# connector.net
KiCad netlist of a schematic drawn in Altium Designer
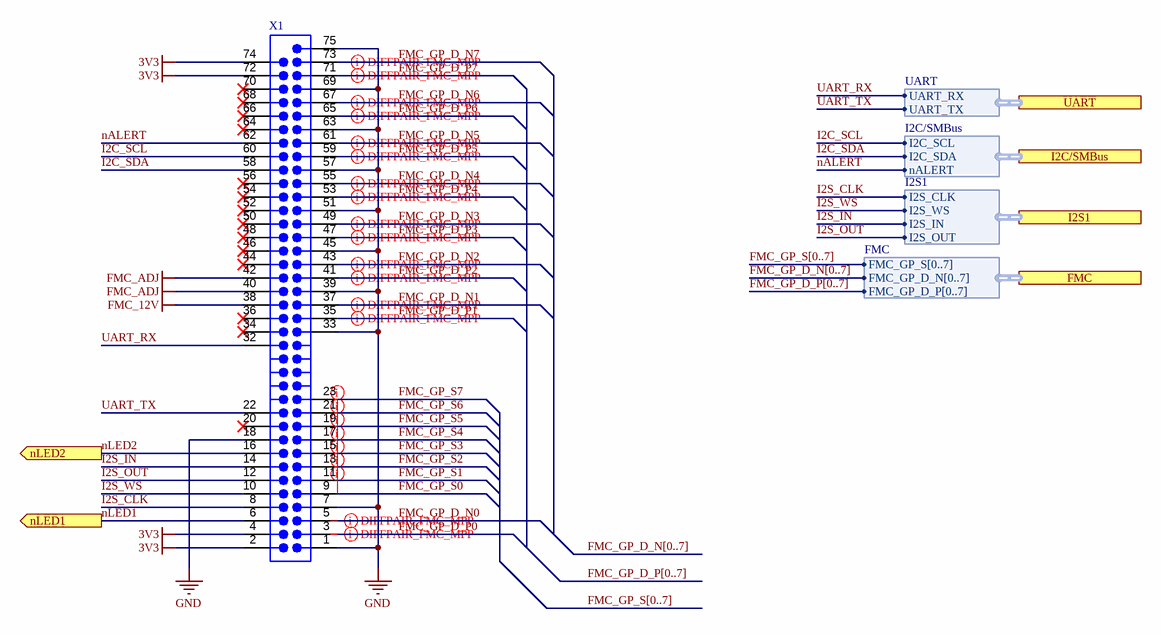
[diagram p0: connector.SchDoc]

(export (version "E")
  (design (tool "Eeschema 10.0.6"))
  (components
    (comp (ref "X1")
      (value "CONN PWR CARD EDGE PCB SLOT MALE")
      (footprint "CON-67_0.5MM_PCB_SLOT")
      (description "Mates with 2199119-4 - No BOM")
      (libsource (lib "ETHZ Vault") (part "CON-67_0.5mm_PCB_SLOT"))
    )
  )
  (nets
    (net (code "5") (name "/FMC_GP_D_N0") (class "Default")
      (node (ref "X1") (pin "5") (pinfunction "5_5") (pintype "passive"))
    )
    (net (code "6") (name "/FMC_GP_D_N1") (class "Default")
      (node (ref "X1") (pin "37") (pinfunction "37_37") (pintype "passive"))
    )
    (net (code "7") (name "/FMC_GP_D_N2") (class "Default")
      (node (ref "X1") (pin "43") (pinfunction "43_43") (pintype "passive"))
    )
    (net (code "8") (name "/FMC_GP_D_N3") (class "Default")
      (node (ref "X1") (pin "49") (pinfunction "49_49") (pintype "passive"))
    )
    (net (code "9") (name "/FMC_GP_D_N4") (class "Default")
      (node (ref "X1") (pin "55") (pinfunction "55_55") (pintype "passive"))
    )
    (net (code "10") (name "/FMC_GP_D_N5") (class "Default")
      (node (ref "X1") (pin "61") (pinfunction "61_61") (pintype "passive"))
    )
    (net (code "11") (name "/FMC_GP_D_N6") (class "Default")
      (node (ref "X1") (pin "67") (pinfunction "67_67") (pintype "passive"))
    )
    (net (code "12") (name "/FMC_GP_D_N7") (class "Default")
      (node (ref "X1") (pin "73") (pinfunction "73_73") (pintype "passive"))
    )
    (net (code "14") (name "/FMC_GP_D_P0") (class "Default")
      (node (ref "X1") (pin "3") (pinfunction "3_3") (pintype "passive"))
    )
    (net (code "15") (name "/FMC_GP_D_P1") (class "Default")
      (node (ref "X1") (pin "35") (pinfunction "35_35") (pintype "passive"))
    )
    (net (code "16") (name "/FMC_GP_D_P2") (class "Default")
      (node (ref "X1") (pin "41") (pinfunction "41_41") (pintype "passive"))
    )
    (net (code "17") (name "/FMC_GP_D_P3") (class "Default")
      (node (ref "X1") (pin "47") (pinfunction "47_47") (pintype "passive"))
    )
    (net (code "18") (name "/FMC_GP_D_P4") (class "Default")
      (node (ref "X1") (pin "53") (pinfunction "53_53") (pintype "passive"))
    )
    (net (code "19") (name "/FMC_GP_D_P5") (class "Default")
      (node (ref "X1") (pin "59") (pinfunction "59_59") (pintype "passive"))
    )
    (net (code "20") (name "/FMC_GP_D_P6") (class "Default")
      (node (ref "X1") (pin "65") (pinfunction "65_65") (pintype "passive"))
    )
    (net (code "21") (name "/FMC_GP_D_P7") (class "Default")
      (node (ref "X1") (pin "71") (pinfunction "71_71") (pintype "passive"))
    )
    (net (code "23") (name "/FMC_GP_S0") (class "Default")
      (node (ref "X1") (pin "9") (pinfunction "9_9") (pintype "passive"))
    )
    (net (code "24") (name "/FMC_GP_S1") (class "Default")
      (node (ref "X1") (pin "11") (pinfunction "11_11") (pintype "passive"))
    )
    (net (code "25") (name "/FMC_GP_S2") (class "Default")
      (node (ref "X1") (pin "13") (pinfunction "13_13") (pintype "passive"))
    )
    (net (code "26") (name "/FMC_GP_S3") (class "Default")
      (node (ref "X1") (pin "15") (pinfunction "15_15") (pintype "passive"))
    )
    (net (code "27") (name "/FMC_GP_S4") (class "Default")
      (node (ref "X1") (pin "17") (pinfunction "17_17") (pintype "passive"))
    )
    (net (code "28") (name "/FMC_GP_S5") (class "Default")
      (node (ref "X1") (pin "19") (pinfunction "19_19") (pintype "passive"))
    )
    (net (code "29") (name "/FMC_GP_S6") (class "Default")
      (node (ref "X1") (pin "21") (pinfunction "21_21") (pintype "passive"))
    )
    (net (code "30") (name "/FMC_GP_S7") (class "Default")
      (node (ref "X1") (pin "23") (pinfunction "23_23") (pintype "passive"))
    )
    (net (code "32") (name "/I2C_SCL") (class "Default")
      (node (ref "X1") (pin "60") (pinfunction "55_60") (pintype "passive"))
    )
    (net (code "33") (name "/I2C_SDA") (class "Default")
      (node (ref "X1") (pin "58") (pinfunction "54_58") (pintype "passive"))
    )
    (net (code "34") (name "/I2S_CLK") (class "Default")
      (node (ref "X1") (pin "8") (pinfunction "8_8") (pintype "passive"))
    )
    (net (code "35") (name "/I2S_IN") (class "Default")
      (node (ref "X1") (pin "14") (pinfunction "14_14") (pintype "passive"))
    )
    (net (code "36") (name "/I2S_OUT") (class "Default")
      (node (ref "X1") (pin "12") (pinfunction "12_12") (pintype "passive"))
    )
    (net (code "37") (name "/I2S_WS") (class "Default")
      (node (ref "X1") (pin "10") (pinfunction "10_10") (pintype "passive"))
    )
    (net (code "38") (name "/UART_RX") (class "Default")
      (node (ref "X1") (pin "32") (pinfunction "32_32") (pintype "passive"))
    )
    (net (code "39") (name "/UART_TX") (class "Default")
      (node (ref "X1") (pin "22") (pinfunction "22_22") (pintype "passive"))
    )
    (net (code "40") (name "/nALERT") (class "Default")
      (node (ref "X1") (pin "62") (pinfunction "62_62") (pintype "passive"))
    )
    (net (code "41") (name "/nLED1") (class "Default")
      (node (ref "X1") (pin "6") (pinfunction "6_6") (pintype "passive"))
    )
    (net (code "42") (name "/nLED2") (class "Default")
      (node (ref "X1") (pin "16") (pinfunction "16_16") (pintype "passive"))
    )
    (net (code "47") (name "3V3") (class "Default")
      (node (ref "X1") (pin "2") (pinfunction "2_2") (pintype "passive"))
      (node (ref "X1") (pin "4") (pinfunction "4_4") (pintype "passive"))
      (node (ref "X1") (pin "72") (pinfunction "72_72") (pintype "passive"))
      (node (ref "X1") (pin "74") (pinfunction "74_74") (pintype "passive"))
    )
    (net (code "48") (name "FMC_12V") (class "Default")
      (node (ref "X1") (pin "38") (pinfunction "38_38") (pintype "passive"))
    )
    (net (code "49") (name "FMC_ADJ") (class "Default")
      (node (ref "X1") (pin "40") (pinfunction "40_40") (pintype "passive"))
      (node (ref "X1") (pin "42") (pinfunction "42_42") (pintype "passive"))
    )
    (net (code "50") (name "GND") (class "Default")
      (node (ref "X1") (pin "1") (pinfunction "1_1") (pintype "passive"))
      (node (ref "X1") (pin "18") (pinfunction "18_18") (pintype "passive"))
      (node (ref "X1") (pin "33") (pinfunction "33_33") (pintype "passive"))
      (node (ref "X1") (pin "39") (pinfunction "39_39") (pintype "passive"))
      (node (ref "X1") (pin "45") (pinfunction "45_45") (pintype "passive"))
      (node (ref "X1") (pin "51") (pinfunction "51_51") (pintype "passive"))
      (node (ref "X1") (pin "57") (pinfunction "57_57") (pintype "passive"))
      (node (ref "X1") (pin "63") (pinfunction "63_63") (pintype "passive"))
      (node (ref "X1") (pin "69") (pinfunction "69_69") (pintype "passive"))
      (node (ref "X1") (pin "7") (pinfunction "7_7") (pintype "passive"))
      (node (ref "X1") (pin "75") (pinfunction "75_75") (pintype "passive"))
    )
    (net (code "51") (name "unconnected-(X1-51-Pad52)") (class "Default")
      (node (ref "X1") (pin "52") (pinfunction "51_52") (pintype "passive+no_connect"))
    )
    (net (code "52") (name "unconnected-(X1-52-Pad54)") (class "Default")
      (node (ref "X1") (pin "54") (pinfunction "52_54") (pintype "passive+no_connect"))
    )
    (net (code "53") (name "unconnected-(X1-53-Pad56)") (class "Default")
      (node (ref "X1") (pin "56") (pinfunction "53_56") (pintype "passive+no_connect"))
    )
    (net (code "54") (name "unconnected-(X1-Pad20)") (class "Default")
      (node (ref "X1") (pin "20") (pinfunction "20_20") (pintype "passive+no_connect"))
    )
    (net (code "55") (name "unconnected-(X1-Pad34)") (class "Default")
      (node (ref "X1") (pin "34") (pinfunction "34_34") (pintype "passive+no_connect"))
    )
    (net (code "56") (name "unconnected-(X1-Pad36)") (class "Default")
      (node (ref "X1") (pin "36") (pinfunction "36_36") (pintype "passive+no_connect"))
    )
    (net (code "57") (name "unconnected-(X1-Pad44)") (class "Default")
      (node (ref "X1") (pin "44") (pinfunction "44_44") (pintype "passive+no_connect"))
    )
    (net (code "58") (name "unconnected-(X1-Pad46)") (class "Default")
      (node (ref "X1") (pin "46") (pinfunction "46_46") (pintype "passive+no_connect"))
    )
    (net (code "59") (name "unconnected-(X1-Pad48)") (class "Default")
      (node (ref "X1") (pin "48") (pinfunction "48_48") (pintype "passive+no_connect"))
    )
    (net (code "60") (name "unconnected-(X1-Pad50)") (class "Default")
      (node (ref "X1") (pin "50") (pinfunction "50_50") (pintype "passive+no_connect"))
    )
    (net (code "61") (name "unconnected-(X1-Pad64)") (class "Default")
      (node (ref "X1") (pin "64") (pinfunction "64_64") (pintype "passive+no_connect"))
    )
    (net (code "62") (name "unconnected-(X1-Pad66)") (class "Default")
      (node (ref "X1") (pin "66") (pinfunction "66_66") (pintype "passive+no_connect"))
    )
    (net (code "63") (name "unconnected-(X1-Pad68)") (class "Default")
      (node (ref "X1") (pin "68") (pinfunction "68_68") (pintype "passive+no_connect"))
    )
    (net (code "64") (name "unconnected-(X1-Pad70)") (class "Default")
      (node (ref "X1") (pin "70") (pinfunction "70_70") (pintype "passive+no_connect"))
    )
  )
)
